# LEDWithDriver.net
KiCad netlist of a schematic drawn in EAGLE
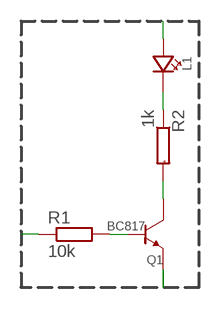
[diagram p0: schematic, sheet 1]

(export (version "E")
  (design (tool "Eeschema 10.0.6"))
  (components
    (comp (ref "L1")
      (value "LED0603")
      (footprint "eagle-import:CHIPLED_0603")
      (libsource (lib "eagle-import") (part "LED0603"))
    )
    (comp (ref "Q1")
      (value "BC817")
      (footprint "eagle-import:SOT23")
      (libsource (lib "eagle-import") (part "TRANSISTOR-NPN-GENERIC-SOT23-BECDEFAULT"))
    )
    (comp (ref "R1")
      (value "10k")
      (footprint "eagle-import:R0603")
      (libsource (lib "eagle-import") (part "R-EU_R0603"))
    )
    (comp (ref "R2")
      (value "1k")
      (footprint "eagle-import:R0603-MARK")
      (libsource (lib "eagle-import") (part "R-EU-MARKEDR0603"))
    )
  )
  (nets
    (net (code "1") (name "Net-(L1-PadC)") (class "Default")
      (node (ref "L1") (pin "C") (pinfunction "C_C") (pintype "bidirectional"))
      (node (ref "R2") (pin "1") (pinfunction "1_1") (pintype "passive"))
    )
    (net (code "2") (name "Net-(Q1-BASE)") (class "Default")
      (node (ref "Q1") (pin "P$1") (pinfunction "BASE_P$1") (pintype "bidirectional"))
      (node (ref "R1") (pin "2") (pinfunction "2_2") (pintype "passive"))
    )
    (net (code "3") (name "Net-(Q1-COLLECTOR)") (class "Default")
      (node (ref "Q1") (pin "P$3") (pinfunction "COLLECTOR_P$3") (pintype "bidirectional"))
      (node (ref "R2") (pin "2") (pinfunction "2_2") (pintype "passive"))
    )
    (net (code "4") (name "unconnected-(L1-PadA)") (class "Default")
      (node (ref "L1") (pin "A") (pinfunction "A_A") (pintype "bidirectional"))
    )
    (net (code "5") (name "unconnected-(Q1-EMITTER-PadP$2)") (class "Default")
      (node (ref "Q1") (pin "P$2") (pinfunction "EMITTER_P$2") (pintype "bidirectional"))
    )
    (net (code "6") (name "unconnected-(R1-Pad1)") (class "Default")
      (node (ref "R1") (pin "1") (pinfunction "1_1") (pintype "passive"))
    )
  )
)
